# 12V_BOOST.net
KiCad netlist of a schematic drawn in Altium Designer
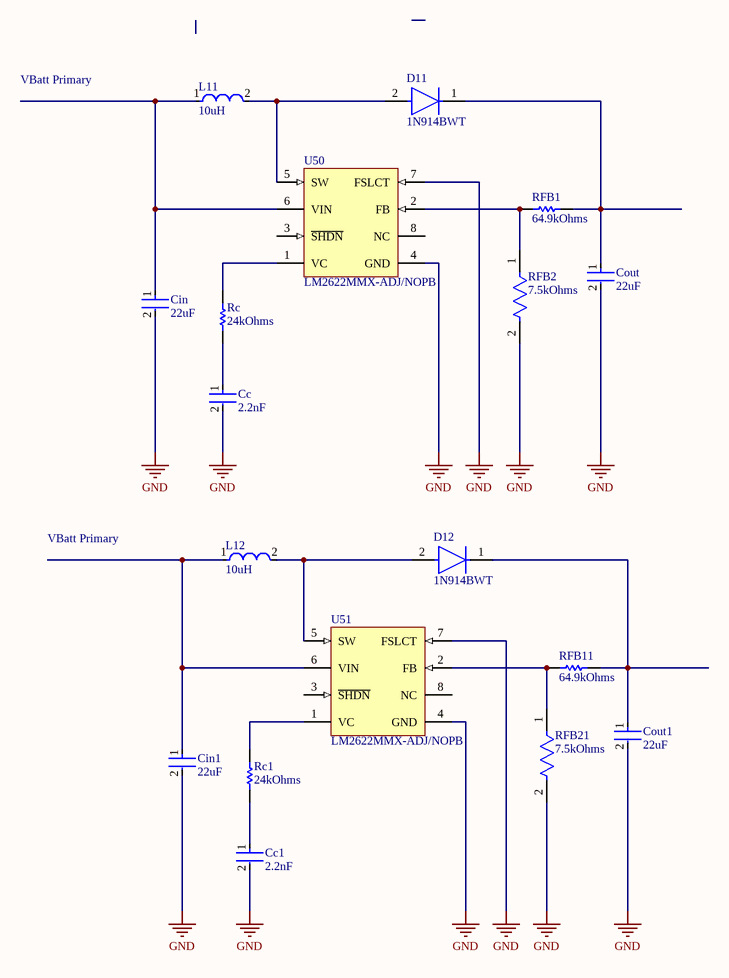
[diagram p0: 12V_BOOST.SchDoc]

(export (version "E")
  (design (tool "Eeschema 10.0.6"))
  (components
    (comp (ref "Cc")
      (value "2.2nF")
      (footprint "FP-C0402-BB-MFG")
      (description "CAP CER 2200PF 25V 5% NP0 0402")
      (fields
        (field (name "OCTOPART") "https://octopart.com/c0402c222j3gactu-kemet-9145102")
        (field (name "MANUFACTURER") "Kemet")
      )
      (libsource (lib "Altium Content Vault") (part "b4654b650e69147ec39a6b967a45e02"))
    )
    (comp (ref "Cc1")
      (value "2.2nF")
      (footprint "FP-C0402-BB-MFG")
      (description "CAP CER 2200PF 25V 5% NP0 0402")
      (fields
        (field (name "OCTOPART") "https://octopart.com/c0402c222j3gactu-kemet-9145102")
        (field (name "MANUFACTURER") "Kemet")
      )
      (libsource (lib "Altium Content Vault") (part "b4654b650e69147ec39a6b967a45e02"))
    )
    (comp (ref "Cin")
      (value "22uF")
      (footprint "FP-CL31-IPC_A")
      (description "Cap Ceramic 22uF 16V X5R ±20% SMD 1206 +85°C Embossed T/R")
      (fields (field (name "TOLERANCE") "20%") (field (name "VOLTAGE") "16V"))
      (libsource (lib "Altium Content Vault") (part "b4654b650e69147ec39a6b967a45e02"))
    )
    (comp (ref "Cin1")
      (value "22uF")
      (footprint "FP-CL31-IPC_A")
      (description "Cap Ceramic 22uF 16V X5R ±20% SMD 1206 +85°C Embossed T/R")
      (fields (field (name "TOLERANCE") "20%") (field (name "VOLTAGE") "16V"))
      (libsource (lib "Altium Content Vault") (part "b4654b650e69147ec39a6b967a45e02"))
    )
    (comp (ref "Cout")
      (value "22uF")
      (footprint "FP-CL31-IPC_A")
      (description "Cap Ceramic 22uF 16V X5R ±20% SMD 1206 +85°C Embossed T/R")
      (fields (field (name "TOLERANCE") "20%") (field (name "VOLTAGE") "16V"))
      (libsource (lib "Altium Content Vault") (part "b4654b650e69147ec39a6b967a45e02"))
    )
    (comp (ref "Cout1")
      (value "22uF")
      (footprint "FP-CL31-IPC_A")
      (description "Cap Ceramic 22uF 16V X5R ±20% SMD 1206 +85°C Embossed T/R")
      (fields (field (name "TOLERANCE") "20%") (field (name "VOLTAGE") "16V"))
      (libsource (lib "Altium Content Vault") (part "b4654b650e69147ec39a6b967a45e02"))
    )
    (comp (ref "D11")
      (value "1N914BWT")
      (footprint "FP-502-01-MFG")
      (description "DIODE GEN PURP 75V 200MA SOD523F")
      (fields
        (field (name "OCTOPART") "https://octopart.com/1n914bwt-on+semiconductor-84323166")
        (field (name "MANUFACTURER") "ON Semiconductor")
      )
      (libsource (lib "Altium Content Vault") (part "d7152d700b627762746794eb795d46e"))
    )
    (comp (ref "D12")
      (value "1N914BWT")
      (footprint "FP-502-01-MFG")
      (description "DIODE GEN PURP 75V 200MA SOD523F")
      (fields
        (field (name "OCTOPART") "https://octopart.com/1n914bwt-on+semiconductor-84323166")
        (field (name "MANUFACTURER") "ON Semiconductor")
      )
      (libsource (lib "Altium Content Vault") (part "d7152d700b627762746794eb795d46e"))
    )
    (comp (ref "L11")
      (value "10uH")
      (footprint "FP-MLZ1608-IPC_C")
      (description "Shielded Multilayer Inductor 10uH ±20% 250mA 1365mΩ SMD 0603")
      (fields (field (name "TOLERANCE") "20%"))
      (libsource (lib "Altium Content Vault") (part "725321dda6339637d4d059423bc1c3c"))
    )
    (comp (ref "L12")
      (value "10uH")
      (footprint "FP-MLZ1608-IPC_C")
      (description "Shielded Multilayer Inductor 10uH ±20% 250mA 1365mΩ SMD 0603")
      (fields (field (name "TOLERANCE") "20%"))
      (libsource (lib "Altium Content Vault") (part "725321dda6339637d4d059423bc1c3c"))
    )
    (comp (ref "Rc")
      (value "24kOhms")
      (footprint "RESC1005X40X25ML05T05")
      (fields (field (name "PART NUMBER") "CRCW040224K0FKED") (field (name "MANUFACTURER") "Vishay Dale"))
      (libsource (lib "Altium Content Vault") (part "RES"))
    )
    (comp (ref "Rc1")
      (value "24kOhms")
      (footprint "RESC1005X40X25ML05T05")
      (fields (field (name "PART NUMBER") "CRCW040224K0FKED") (field (name "MANUFACTURER") "Vishay Dale"))
      (libsource (lib "Altium Content Vault") (part "RES"))
    )
    (comp (ref "RFB1")
      (value "64.9kOhms")
      (footprint "RESC3216X70X50NL05T20")
      (fields (field (name "PART NUMBER") "ERJ-8ENF64R9V") (field (name "MANUFACTURER") "Panasonic"))
      (libsource (lib "Altium Content Vault") (part "RES"))
    )
    (comp (ref "RFB2")
      (value "7.5kOhms")
      (footprint "FP-ERJ3EK-MFG")
      (description "RES SMD 7.5K OHM 1% 1/10W 0603")
      (fields (field (name "TOLERANCE") "1%"))
      (libsource (lib "Altium Content Vault") (part "1029c3af85768c4190bb7ad29bc67b5"))
    )
    (comp (ref "RFB11")
      (value "64.9kOhms")
      (footprint "RESC3216X70X50NL05T20")
      (fields (field (name "PART NUMBER") "ERJ-8ENF64R9V") (field (name "MANUFACTURER") "Panasonic"))
      (libsource (lib "Altium Content Vault") (part "RES"))
    )
    (comp (ref "RFB21")
      (value "7.5kOhms")
      (footprint "FP-ERJ3EK-MFG")
      (description "RES SMD 7.5K OHM 1% 1/10W 0603")
      (fields (field (name "TOLERANCE") "1%"))
      (libsource (lib "Altium Content Vault") (part "1029c3af85768c4190bb7ad29bc67b5"))
    )
    (comp (ref "U50")
      (value "LM2622MMX-ADJ/NOPB")
      (footprint "DGK0008A_M")
      (description "600kHz/1.3MHz Step-up PWM DC/DC Converter, 8-pin MSOP, Pb-Free")
      (fields (field (name "MANUFACTURER") "Texas Instruments"))
      (libsource (lib "Altium Content Vault") (part "PM-CNTL-LM2622MM-8"))
    )
    (comp (ref "U51")
      (value "LM2622MMX-ADJ/NOPB")
      (footprint "DGK0008A_M")
      (description "600kHz/1.3MHz Step-up PWM DC/DC Converter, 8-pin MSOP, Pb-Free")
      (fields (field (name "MANUFACTURER") "Texas Instruments"))
      (libsource (lib "Altium Content Vault") (part "PM-CNTL-LM2622MM-8"))
    )
  )
  (nets
    (net (code "1") (name "GND") (class "Default")
      (node (ref "Cc") (pin "2") (pinfunction "2_2") (pintype "passive"))
      (node (ref "Cc1") (pin "2") (pinfunction "2_2") (pintype "passive"))
      (node (ref "Cin") (pin "2") (pinfunction "2_2") (pintype "passive"))
      (node (ref "Cin1") (pin "2") (pinfunction "2_2") (pintype "passive"))
      (node (ref "Cout") (pin "2") (pinfunction "2_2") (pintype "passive"))
      (node (ref "Cout1") (pin "2") (pinfunction "2_2") (pintype "passive"))
      (node (ref "RFB2") (pin "2") (pinfunction "2_2") (pintype "passive"))
      (node (ref "RFB21") (pin "2") (pinfunction "2_2") (pintype "passive"))
      (node (ref "U50") (pin "4") (pinfunction "GND_4") (pintype "power_in"))
      (node (ref "U50") (pin "7") (pinfunction "FSLCT_7") (pintype "input"))
      (node (ref "U51") (pin "4") (pinfunction "GND_4") (pintype "power_in"))
      (node (ref "U51") (pin "7") (pinfunction "FSLCT_7") (pintype "input"))
    )
    (net (code "2") (name "Net-(Cc-Pad1)") (class "Default")
      (node (ref "Cc") (pin "1") (pinfunction "1_1") (pintype "passive"))
      (node (ref "Rc") (pin "2") (pinfunction "2_2") (pintype "passive"))
    )
    (net (code "3") (name "Net-(Cc1-Pad1)") (class "Default")
      (node (ref "Cc1") (pin "1") (pinfunction "1_1") (pintype "passive"))
      (node (ref "Rc1") (pin "2") (pinfunction "2_2") (pintype "passive"))
    )
    (net (code "4") (name "Net-(D11-A)") (class "Default")
      (node (ref "D11") (pin "2") (pinfunction "A_2") (pintype "passive"))
      (node (ref "L11") (pin "2") (pinfunction "2_2") (pintype "passive"))
      (node (ref "U50") (pin "5") (pinfunction "SW_5") (pintype "input"))
    )
    (net (code "5") (name "Net-(D11-C)") (class "Default")
      (node (ref "Cout") (pin "1") (pinfunction "1_1") (pintype "passive"))
      (node (ref "D11") (pin "1") (pinfunction "C_1") (pintype "passive"))
      (node (ref "RFB1") (pin "2") (pinfunction "2_2") (pintype "passive"))
    )
    (net (code "6") (name "Net-(D12-A)") (class "Default")
      (node (ref "D12") (pin "2") (pinfunction "A_2") (pintype "passive"))
      (node (ref "L12") (pin "2") (pinfunction "2_2") (pintype "passive"))
      (node (ref "U51") (pin "5") (pinfunction "SW_5") (pintype "input"))
    )
    (net (code "7") (name "Net-(D12-C)") (class "Default")
      (node (ref "Cout1") (pin "1") (pinfunction "1_1") (pintype "passive"))
      (node (ref "D12") (pin "1") (pinfunction "C_1") (pintype "passive"))
      (node (ref "RFB11") (pin "2") (pinfunction "2_2") (pintype "passive"))
    )
    (net (code "8") (name "Net-(U50-FB)") (class "Default")
      (node (ref "RFB1") (pin "1") (pinfunction "1_1") (pintype "passive"))
      (node (ref "RFB2") (pin "1") (pinfunction "1_1") (pintype "passive"))
      (node (ref "U50") (pin "2") (pinfunction "FB_2") (pintype "input"))
    )
    (net (code "9") (name "Net-(U50-VC)") (class "Default")
      (node (ref "Rc") (pin "1") (pinfunction "1_1") (pintype "passive"))
      (node (ref "U50") (pin "1") (pinfunction "VC_1") (pintype "power_in"))
    )
    (net (code "10") (name "Net-(U50-VIN)") (class "Default")
      (node (ref "Cin") (pin "1") (pinfunction "1_1") (pintype "passive"))
      (node (ref "L11") (pin "1") (pinfunction "1_1") (pintype "passive"))
      (node (ref "U50") (pin "6") (pinfunction "VIN_6") (pintype "power_in"))
    )
    (net (code "11") (name "Net-(U51-FB)") (class "Default")
      (node (ref "RFB11") (pin "1") (pinfunction "1_1") (pintype "passive"))
      (node (ref "RFB21") (pin "1") (pinfunction "1_1") (pintype "passive"))
      (node (ref "U51") (pin "2") (pinfunction "FB_2") (pintype "input"))
    )
    (net (code "12") (name "Net-(U51-VC)") (class "Default")
      (node (ref "Rc1") (pin "1") (pinfunction "1_1") (pintype "passive"))
      (node (ref "U51") (pin "1") (pinfunction "VC_1") (pintype "power_in"))
    )
    (net (code "13") (name "Net-(U51-VIN)") (class "Default")
      (node (ref "Cin1") (pin "1") (pinfunction "1_1") (pintype "passive"))
      (node (ref "L12") (pin "1") (pinfunction "1_1") (pintype "passive"))
      (node (ref "U51") (pin "6") (pinfunction "VIN_6") (pintype "power_in"))
    )
    (net (code "14") (name "unconnected-(U50-NC-Pad8)") (class "Default")
      (node (ref "U50") (pin "8") (pinfunction "NC_8") (pintype "passive"))
    )
    (net (code "15") (name "unconnected-(U50-~{SHDN}-Pad3)") (class "Default")
      (node (ref "U50") (pin "3") (pinfunction "~{SHDN}_3") (pintype "input"))
    )
    (net (code "16") (name "unconnected-(U51-NC-Pad8)") (class "Default")
      (node (ref "U51") (pin "8") (pinfunction "NC_8") (pintype "passive"))
    )
    (net (code "17") (name "unconnected-(U51-~{SHDN}-Pad3)") (class "Default")
      (node (ref "U51") (pin "3") (pinfunction "~{SHDN}_3") (pintype "input"))
    )
  )
)
